# FLC-148_-_Poti_FFC.net
KiCad netlist of a schematic drawn in EAGLE
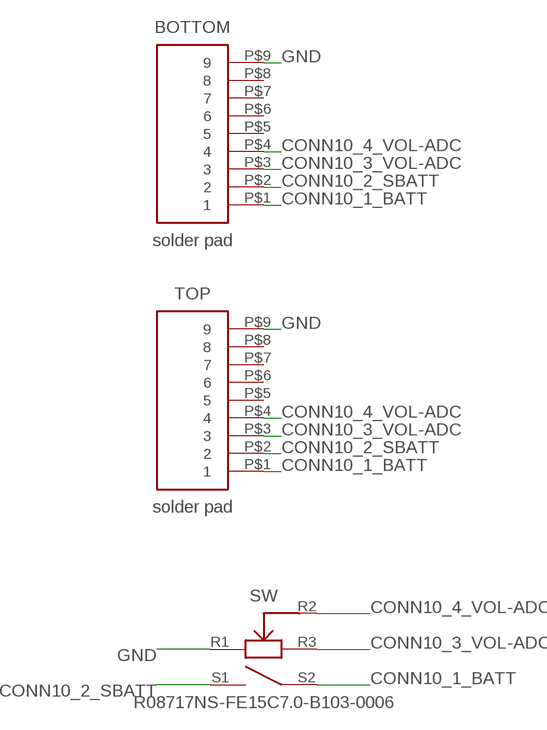
[diagram p0: schematic, sheet 1]

(export (version "E")
  (design (tool "Eeschema 10.0.6"))
  (components
    (comp (ref "BOTTOM")
      (value "solder pad")
      (footprint "eagle-import:SMD")
      (libsource (lib "eagle-import") (part "FFC_END-9P_1MM_PITCH"))
    )
    (comp (ref "SW")
      (value "R08717NS-FE15C7.0-B103-0006")
      (footprint "eagle-import:TH")
      (libsource (lib "eagle-import") (part "R08717NS-FE15C7.0-B103-0006"))
    )
    (comp (ref "TOP")
      (value "solder pad")
      (footprint "eagle-import:SMD")
      (libsource (lib "eagle-import") (part "FFC_END-9P_1MM_PITCH"))
    )
  )
  (nets
    (net (code "1") (name "/CONN10_1_BATT") (class "Default")
      (node (ref "BOTTOM") (pin "P$1") (pinfunction "1_P$1") (pintype "bidirectional"))
      (node (ref "SW") (pin "S2") (pinfunction "S2_S2") (pintype "bidirectional"))
      (node (ref "TOP") (pin "P$1") (pinfunction "1_P$1") (pintype "bidirectional"))
    )
    (net (code "2") (name "/CONN10_2_SBATT") (class "Default")
      (node (ref "BOTTOM") (pin "P$2") (pinfunction "2_P$2") (pintype "bidirectional"))
      (node (ref "SW") (pin "S1") (pinfunction "S1_S1") (pintype "bidirectional"))
      (node (ref "TOP") (pin "P$2") (pinfunction "2_P$2") (pintype "bidirectional"))
    )
    (net (code "3") (name "/CONN10_3_VOL-ADC") (class "Default")
      (node (ref "BOTTOM") (pin "P$3") (pinfunction "3_P$3") (pintype "bidirectional"))
      (node (ref "SW") (pin "R3") (pinfunction "R3_R3") (pintype "bidirectional"))
      (node (ref "TOP") (pin "P$3") (pinfunction "3_P$3") (pintype "bidirectional"))
    )
    (net (code "4") (name "/CONN10_4_VOL-ADC") (class "Default")
      (node (ref "BOTTOM") (pin "P$4") (pinfunction "4_P$4") (pintype "bidirectional"))
      (node (ref "SW") (pin "R2") (pinfunction "R2_R2") (pintype "bidirectional"))
      (node (ref "TOP") (pin "P$4") (pinfunction "4_P$4") (pintype "bidirectional"))
    )
    (net (code "5") (name "/GND") (class "Default")
      (node (ref "BOTTOM") (pin "P$9") (pinfunction "9_P$9") (pintype "bidirectional"))
      (node (ref "SW") (pin "R1") (pinfunction "R1_R1") (pintype "bidirectional"))
      (node (ref "TOP") (pin "P$9") (pinfunction "9_P$9") (pintype "bidirectional"))
    )
    (net (code "6") (name "unconnected-(BOTTOM-5-PadP$5)") (class "Default")
      (node (ref "BOTTOM") (pin "P$5") (pinfunction "5_P$5") (pintype "bidirectional"))
    )
    (net (code "7") (name "unconnected-(BOTTOM-6-PadP$6)") (class "Default")
      (node (ref "BOTTOM") (pin "P$6") (pinfunction "6_P$6") (pintype "bidirectional"))
    )
    (net (code "8") (name "unconnected-(BOTTOM-7-PadP$7)") (class "Default")
      (node (ref "BOTTOM") (pin "P$7") (pinfunction "7_P$7") (pintype "bidirectional"))
    )
    (net (code "9") (name "unconnected-(BOTTOM-8-PadP$8)") (class "Default")
      (node (ref "BOTTOM") (pin "P$8") (pinfunction "8_P$8") (pintype "bidirectional"))
    )
    (net (code "10") (name "unconnected-(TOP-5-PadP$5)") (class "Default")
      (node (ref "TOP") (pin "P$5") (pinfunction "5_P$5") (pintype "bidirectional"))
    )
    (net (code "11") (name "unconnected-(TOP-6-PadP$6)") (class "Default")
      (node (ref "TOP") (pin "P$6") (pinfunction "6_P$6") (pintype "bidirectional"))
    )
    (net (code "12") (name "unconnected-(TOP-7-PadP$7)") (class "Default")
      (node (ref "TOP") (pin "P$7") (pinfunction "7_P$7") (pintype "bidirectional"))
    )
    (net (code "13") (name "unconnected-(TOP-8-PadP$8)") (class "Default")
      (node (ref "TOP") (pin "P$8") (pinfunction "8_P$8") (pintype "bidirectional"))
    )
  )
)
